# chess_module_connectors.net
KiCad netlist of a schematic drawn in Altium Designer
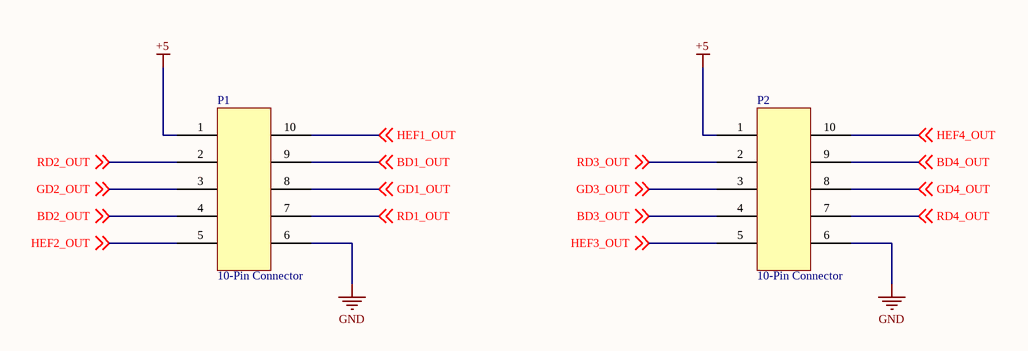
[diagram p0: chess_module_connectors.SchDoc]

(export (version "E")
  (design (tool "Eeschema 10.0.6"))
  (components
    (comp (ref "P1") (value "10-Pin Connector") (libsource (lib "chess_module") (part "10-Pin Connector")))
    (comp (ref "P2") (value "10-Pin Connector") (libsource (lib "chess_module") (part "10-Pin Connector")))
  )
  (nets
    (net (code "1") (name "+5") (class "Default")
      (node (ref "P1") (pin "1") (pintype "passive"))
      (node (ref "P2") (pin "1") (pintype "passive"))
    )
    (net (code "2") (name "BD1_OUT") (class "Default") (node (ref "P1") (pin "9") (pintype "passive")))
    (net (code "3") (name "BD2_OUT") (class "Default") (node (ref "P1") (pin "4") (pintype "passive")))
    (net (code "4") (name "BD3_OUT") (class "Default") (node (ref "P2") (pin "4") (pintype "passive")))
    (net (code "5") (name "BD4_OUT") (class "Default") (node (ref "P2") (pin "9") (pintype "passive")))
    (net (code "6") (name "GD1_OUT") (class "Default") (node (ref "P1") (pin "8") (pintype "passive")))
    (net (code "7") (name "GD2_OUT") (class "Default") (node (ref "P1") (pin "3") (pintype "passive")))
    (net (code "8") (name "GD3_OUT") (class "Default") (node (ref "P2") (pin "3") (pintype "passive")))
    (net (code "9") (name "GD4_OUT") (class "Default") (node (ref "P2") (pin "8") (pintype "passive")))
    (net (code "10") (name "GND") (class "Default")
      (node (ref "P1") (pin "6") (pintype "passive"))
      (node (ref "P2") (pin "6") (pintype "passive"))
    )
    (net (code "11") (name "HEF1_OUT") (class "Default") (node (ref "P1") (pin "10") (pintype "passive")))
    (net (code "12") (name "HEF2_OUT") (class "Default") (node (ref "P1") (pin "5") (pintype "passive")))
    (net (code "13") (name "HEF3_OUT") (class "Default") (node (ref "P2") (pin "5") (pintype "passive")))
    (net (code "14") (name "HEF4_OUT") (class "Default") (node (ref "P2") (pin "10") (pintype "passive")))
    (net (code "15") (name "RD1_OUT") (class "Default") (node (ref "P1") (pin "7") (pintype "passive")))
    (net (code "16") (name "RD2_OUT") (class "Default") (node (ref "P1") (pin "2") (pintype "passive")))
    (net (code "17") (name "RD3_OUT") (class "Default") (node (ref "P2") (pin "2") (pintype "passive")))
    (net (code "18") (name "RD4_OUT") (class "Default") (node (ref "P2") (pin "7") (pintype "passive")))
  )
)
